# Sensors_and_peripherals.net
KiCad netlist of a schematic drawn in Altium Designer
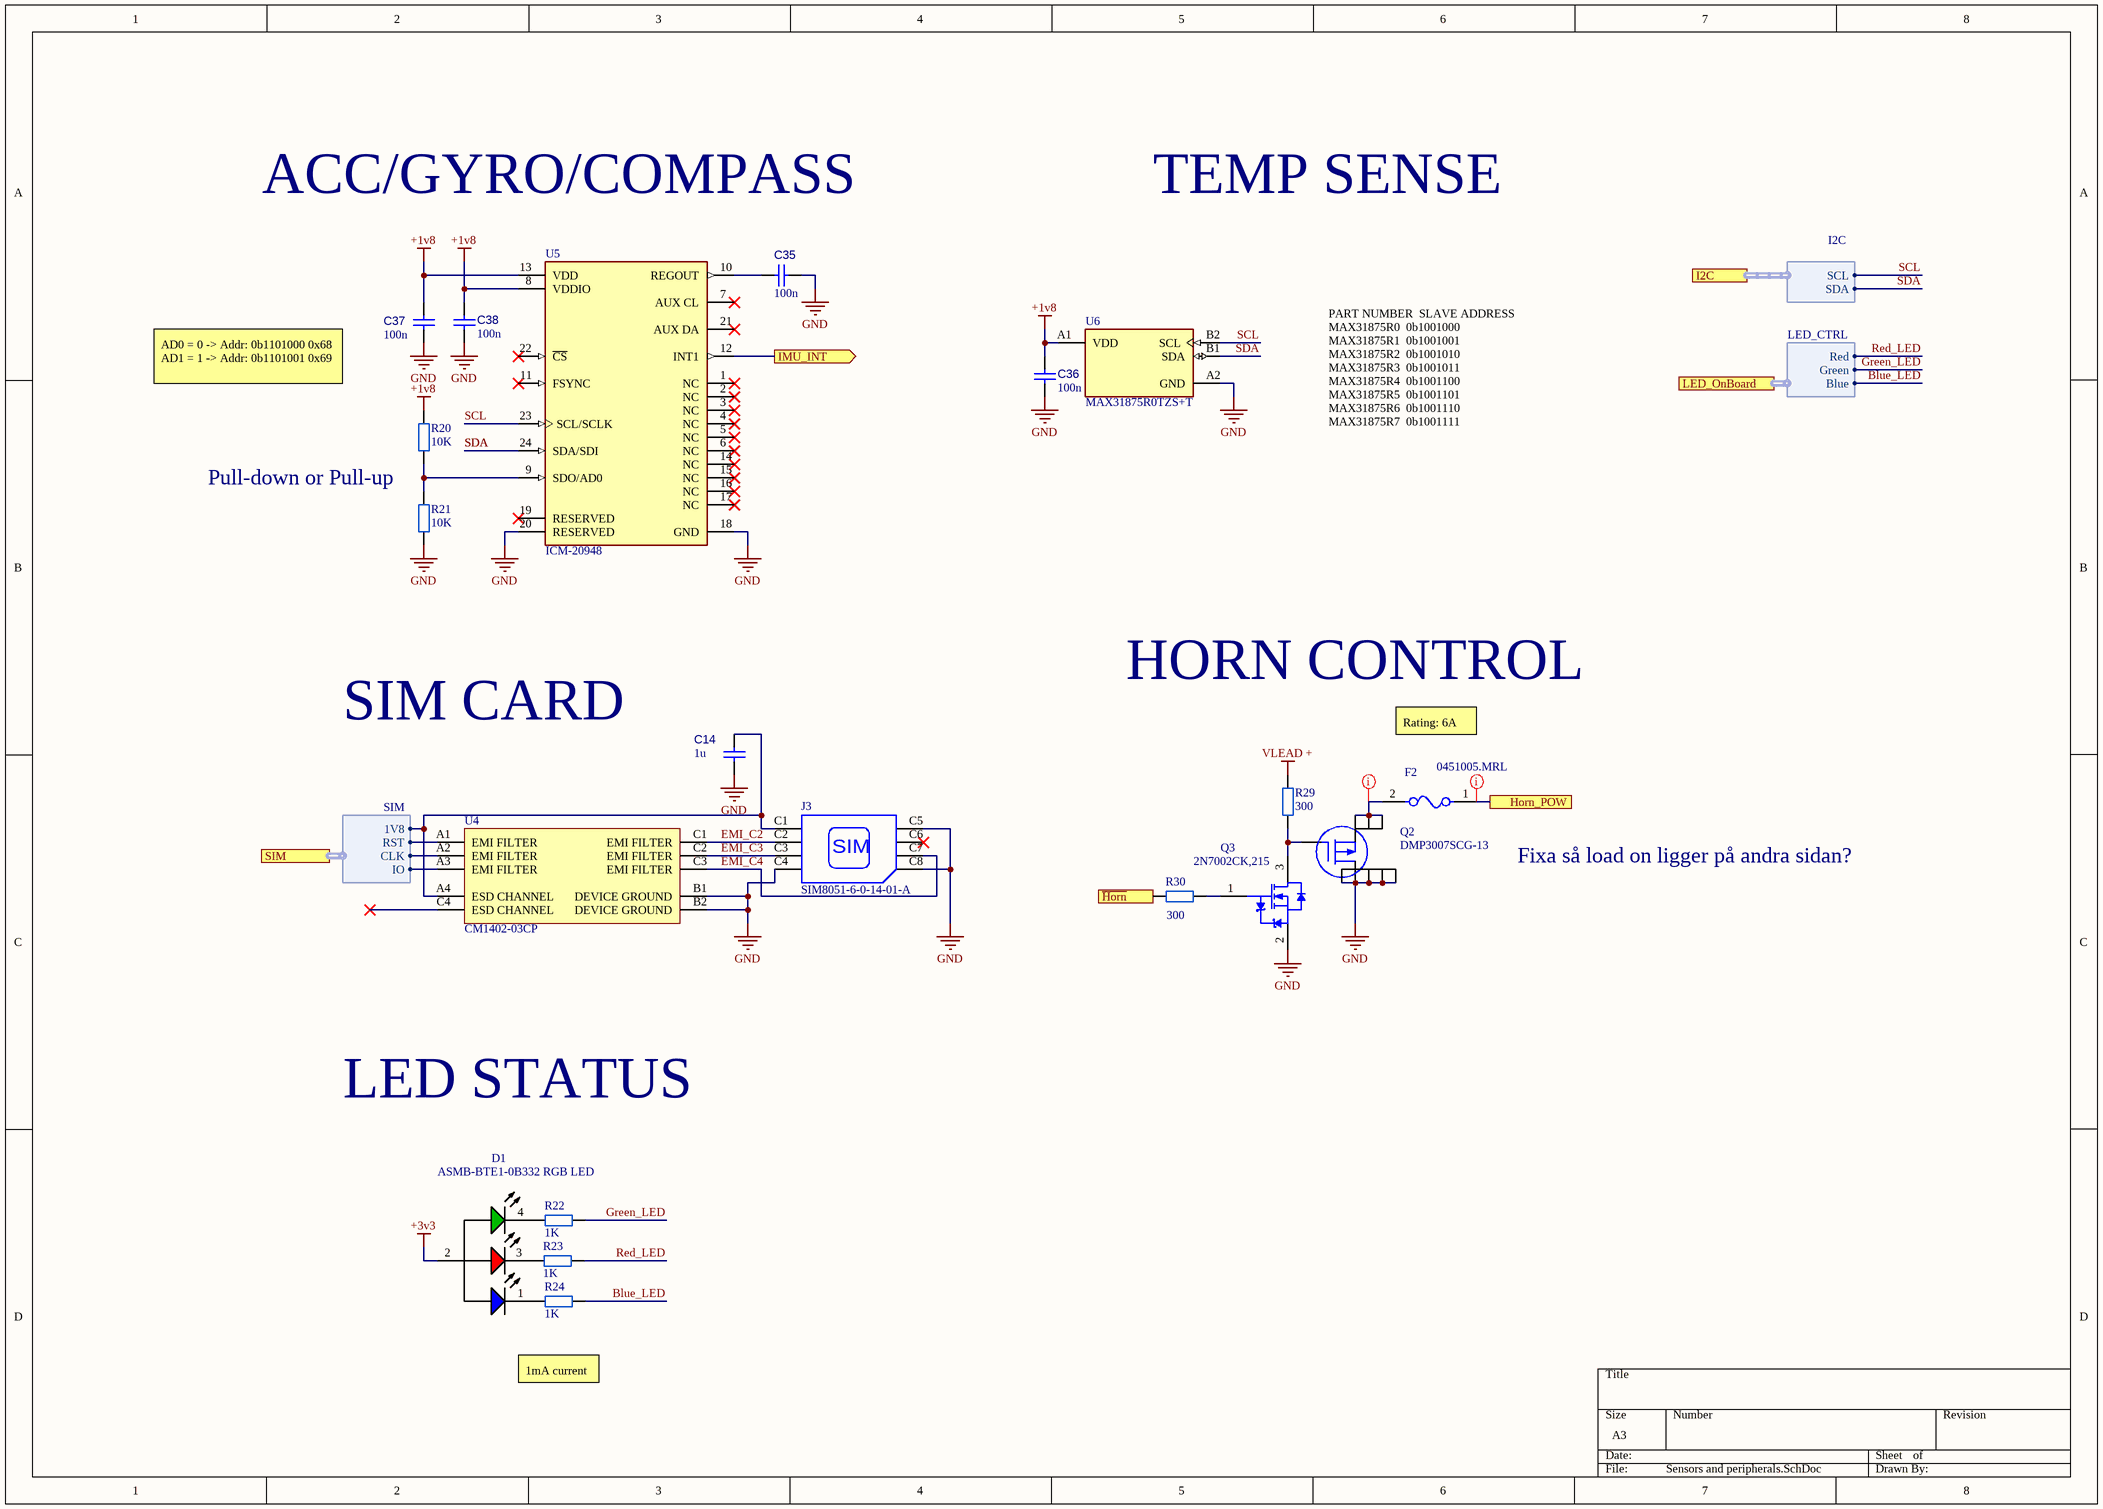
[diagram p0: Sensors and peripherals.SchDoc]

(export (version "E")
  (design (tool "Eeschema 10.0.6"))
  (components
    (comp (ref "C14")
      (value "1u")
      (footprint "CAPC1608X90X40LL10T20 HD")
      (description "Chip Capacitor, 0603 (1608 Metric)")
      (fields (field (name "TOLERANCE") "?%") (field (name "Comment") "Capacitor 0603"))
      (libsource (lib "Motonaut") (part "CAP-NP-2"))
    )
    (comp (ref "C35")
      (value "100n")
      (footprint "CAPC1005X55X25LL05T10 HD")
      (description "Chip Capacitor, 0402 (1005 Metric)")
      (fields (field (name "TOLERANCE") "?%") (field (name "Comment") "Capacitor 0402"))
      (libsource (lib "Motonaut") (part "CAP-NP-2"))
    )
    (comp (ref "C36")
      (value "100n")
      (footprint "CAPC1005X55X25LL05T10 HD")
      (description "Chip Capacitor, 0402 (1005 Metric)")
      (fields (field (name "TOLERANCE") "?%") (field (name "Comment") "Capacitor 0402"))
      (libsource (lib "Motonaut") (part "CAP-NP-2"))
    )
    (comp (ref "C37")
      (value "100n")
      (footprint "CAPC1005X55X25LL05T10 HD")
      (description "Chip Capacitor, 0402 (1005 Metric)")
      (fields (field (name "TOLERANCE") "?%") (field (name "Comment") "Capacitor 0402"))
      (libsource (lib "Motonaut") (part "CAP-NP-2"))
    )
    (comp (ref "C38")
      (value "100n")
      (footprint "CAPC1005X55X25LL05T10 HD")
      (description "Chip Capacitor, 0402 (1005 Metric)")
      (fields (field (name "TOLERANCE") "?%") (field (name "Comment") "Capacitor 0402"))
      (libsource (lib "Motonaut") (part "CAP-NP-2"))
    )
    (comp (ref "D1")
      (value "ASMB-BTE1-0B332 RGB LED")
      (footprint "FP-ASMB-BTE1-0B332-MFG")
      (description "LED RGB DIFFUSED 4PLCC SMD")
      (fields
        (field (name "MANUFACTURER PART NUMBER") "ASMB-BTE1-0B332")
        (field (name "OCTOPART") "https://octopart.com/asmb-bte1-0b332-broadcom-71127192")
      )
      (libsource (lib "Motonaut") (part "ASMB-BTE1-0B332 RGB LED"))
    )
    (comp (ref "F2")
      (value "0451005.MRL")
      (footprint "FP-0451-MFG")
      (description "FUSE BRD MNT 5A 125VAC/VDC 2SMD")
      (fields
        (field (name "OCTOPART") "https://octopart.com/0451005.mrl-littelfuse-566389")
        (field (name "MANUFACTURER") "Littelfuse Inc")
      )
      (libsource (lib "Altium Content Vault") (part "5bcf9b9f640e542cf0359d10258e979"))
    )
    (comp (ref "J3")
      (value "SIM8051-6-0-14-01-A")
      (footprint "FP-SIM8051-6-0-14-01-A-MFG")
      (description "Push-Pull 6P 1.35mmH 3µ\" gold with peg and logo Nano SIM Card Connector")
      (libsource (lib "Motonaut") (part "CN-2P-2F-SIM6"))
    )
    (comp (ref "Q2")
      (value "DMP3007SCG-13")
      (footprint "DMP3007SCG13")
      (description "Trans MOSFET P-CH 30V 50A 8-Pin VDFN EP T/R")
      (fields (field (name "MOUSER PART NUMBER") "621-DMP3007SCG-13"))
      (libsource (lib "Motonaut") (part "TRANS-MOSFET-3"))
    )
    (comp (ref "Q3")
      (value "2N7002CK,215")
      (footprint "NXP-SOT23_N")
      (description "N-Channel Trench MOSFET, 60 V, 0.3 A, -55 to 150 degC, 3-Pin SOT23, Tape and Reel")
      (fields (field (name "MANUFACTURER") "NXP Semiconductors"))
      (libsource (lib "Altium Content Vault") (part "NXP-NMOS-GSD-3_A"))
    )
    (comp (ref "R20")
      (value "10K")
      (footprint "RESC1005X40X25LL10T10 HD")
      (description "Resistor 0403")
      (libsource (lib "Motonaut") (part "Resistor EU"))
    )
    (comp (ref "R21")
      (value "10K")
      (footprint "RESC1005X40X25LL10T10 HD")
      (description "Resistor 0403")
      (libsource (lib "Motonaut") (part "Resistor EU"))
    )
    (comp (ref "R22")
      (value "1K")
      (footprint "RESC1005X40X25LL10T10 HD")
      (description "Resistor 0403")
      (libsource (lib "Motonaut") (part "Resistor EU"))
    )
    (comp (ref "R23")
      (value "1K")
      (footprint "RESC1005X40X25LL10T10 HD")
      (description "Resistor 0403")
      (libsource (lib "Motonaut") (part "Resistor EU"))
    )
    (comp (ref "R24")
      (value "1K")
      (footprint "RESC1005X40X25LL10T10 HD")
      (description "Resistor 0403")
      (libsource (lib "Motonaut") (part "Resistor EU"))
    )
    (comp (ref "R29")
      (value "300")
      (footprint "RESC1608X55X25ML10T15")
      (description "Resistor 0603")
      (libsource (lib "Motonaut") (part "Resistor EU"))
    )
    (comp (ref "R30")
      (value "300")
      (footprint "RESC1608X55X25ML10T15")
      (description "Resistor 0603")
      (libsource (lib "Motonaut") (part "Resistor EU"))
    )
    (comp (ref "U4")
      (value "CM1402-03CP")
      (footprint "ONSC-WLCSP-10-567BL-01")
      (fields (field (name "MANUFACTURER") "On Semiconductor"))
      (libsource (lib "Altium Content Vault") (part "ONSC-EMI-CXXXXX-10"))
    )
    (comp (ref "U5")
      (value "ICM-20948")
      (footprint "FP-ICM-20948-IPC_A")
      (description "IMU ACCEL/GYRO/COMPI2C/SPI 24QFN")
      (libsource (lib "Motonaut") (part "f55aed9b0ea5cc58222276bed130340"))
    )
    (comp (ref "U6")
      (value "MAX31875R0TZS+T")
      (footprint "FP-Z40C0-1-MFG")
      (description "The MAX31875 is a ±1°C-Accurate Local Temperature Sensor with I2C/SMBus Interface.")
      (libsource (lib "Motonaut") (part "0ce7e0ec6f8436ba6b8f7797b006597"))
    )
  )
  (nets
    (net (code "4") (name "+1v8") (class "Default")
      (node (ref "C36") (pin "2") (pinfunction "2_2") (pintype "passive"))
      (node (ref "C37") (pin "2") (pinfunction "2_2") (pintype "passive"))
      (node (ref "C38") (pin "2") (pinfunction "2_2") (pintype "passive"))
      (node (ref "R20") (pin "2") (pinfunction "2_2") (pintype "passive"))
      (node (ref "U5") (pin "13") (pinfunction "VDD_13") (pintype "power_in"))
      (node (ref "U5") (pin "8") (pinfunction "VDDIO_8") (pintype "power_in"))
      (node (ref "U6") (pin "A1") (pinfunction "VDD_A1") (pintype "power_in"))
    )
    (net (code "5") (name "+3v3") (class "Default")
      (node (ref "D1") (pin "2") (pinfunction "Common_Anode_2") (pintype "passive"))
    )
    (net (code "6") (name "/1V8") (class "Default")
      (node (ref "C14") (pin "2") (pinfunction "2_2") (pintype "passive"))
      (node (ref "J3") (pin "C1") (pinfunction "VCC_C1") (pintype "power_in"))
      (node (ref "U4") (pin "A4") (pinfunction "ESD_CHANNEL_A4") (pintype "power_in"))
    )
    (net (code "7") (name "/Blue_LED") (class "Default")
      (node (ref "R24") (pin "1") (pinfunction "1_1") (pintype "passive"))
    )
    (net (code "8") (name "/CLK") (class "Default")
      (node (ref "U4") (pin "A2") (pinfunction "EMI_FILTER_A2") (pintype "passive"))
    )
    (net (code "9") (name "/EMI_C2") (class "Default")
      (node (ref "J3") (pin "C2") (pinfunction "RST_C2") (pintype "passive"))
      (node (ref "U4") (pin "C1") (pinfunction "EMI_FILTER_C1") (pintype "passive"))
    )
    (net (code "10") (name "/EMI_C3") (class "Default")
      (node (ref "J3") (pin "C3") (pinfunction "CLK_C3") (pintype "passive"))
      (node (ref "U4") (pin "C2") (pinfunction "EMI_FILTER_C2") (pintype "passive"))
    )
    (net (code "11") (name "/EMI_C4") (class "Default")
      (node (ref "J3") (pin "C7") (pinfunction "I/O_C7") (pintype "passive"))
      (node (ref "U4") (pin "C3") (pinfunction "EMI_FILTER_C3") (pintype "passive"))
    )
    (net (code "12") (name "/Green_LED") (class "Default")
      (node (ref "R22") (pin "1") (pinfunction "1_1") (pintype "passive"))
    )
    (net (code "13") (name "/Horn_POW") (class "Default")
      (node (ref "F2") (pin "1") (pinfunction "1_1") (pintype "passive"))
    )
    (net (code "14") (name "/IMU_INT") (class "Default")
      (node (ref "U5") (pin "12") (pinfunction "INT1_12") (pintype "output"))
    )
    (net (code "15") (name "/IO") (class "Default")
      (node (ref "U4") (pin "A3") (pinfunction "EMI_FILTER_A3") (pintype "passive"))
    )
    (net (code "16") (name "/RST") (class "Default")
      (node (ref "U4") (pin "A1") (pinfunction "EMI_FILTER_A1") (pintype "passive"))
    )
    (net (code "17") (name "/Red_LED") (class "Default")
      (node (ref "R23") (pin "1") (pinfunction "1_1") (pintype "passive"))
    )
    (net (code "18") (name "/SCL") (class "Default")
      (node (ref "U5") (pin "23") (pinfunction "SCL/SCLK_23") (pintype "input"))
      (node (ref "U6") (pin "B2") (pinfunction "SCL_B2") (pintype "input"))
    )
    (net (code "19") (name "/SDA") (class "Default")
      (node (ref "U5") (pin "24") (pinfunction "SDA/SDI_24") (pintype "input"))
      (node (ref "U6") (pin "B1") (pinfunction "SDA_B1") (pintype "bidirectional"))
    )
    (net (code "23") (name "/~{Horn}") (class "Default")
      (node (ref "R30") (pin "1") (pinfunction "1_1") (pintype "passive"))
    )
    (net (code "24") (name "GND") (class "Default")
      (node (ref "C14") (pin "1") (pinfunction "1_1") (pintype "passive"))
      (node (ref "C35") (pin "1") (pinfunction "1_1") (pintype "passive"))
      (node (ref "C36") (pin "1") (pinfunction "1_1") (pintype "passive"))
      (node (ref "C37") (pin "1") (pinfunction "1_1") (pintype "passive"))
      (node (ref "C38") (pin "1") (pinfunction "1_1") (pintype "passive"))
      (node (ref "J3") (pin "C4") (pinfunction "SHLD_C4") (pintype "passive"))
      (node (ref "J3") (pin "C5") (pinfunction "GND_C5") (pintype "power_in"))
      (node (ref "J3") (pin "C8") (pinfunction "SHLD_C8") (pintype "passive"))
      (node (ref "Q2") (pin "5") (pinfunction "D_5") (pintype "passive"))
      (node (ref "Q2") (pin "6") (pinfunction "D_6") (pintype "passive"))
      (node (ref "Q2") (pin "7") (pinfunction "D_7") (pintype "passive"))
      (node (ref "Q2") (pin "8") (pinfunction "D_8") (pintype "passive"))
      (node (ref "Q2") (pin "9") (pinfunction "D_9") (pintype "passive"))
      (node (ref "Q3") (pin "2") (pinfunction "S_2") (pintype "passive"))
      (node (ref "R21") (pin "1") (pinfunction "1_1") (pintype "passive"))
      (node (ref "U4") (pin "B1") (pinfunction "DEVICE_GROUND_B1") (pintype "power_in"))
      (node (ref "U4") (pin "B2") (pinfunction "DEVICE_GROUND_B2") (pintype "power_in"))
      (node (ref "U5") (pin "18") (pinfunction "GND_18") (pintype "power_in"))
      (node (ref "U5") (pin "20") (pinfunction "RESERVED_20") (pintype "passive"))
      (node (ref "U6") (pin "A2") (pinfunction "GND_A2") (pintype "power_in"))
    )
    (net (code "25") (name "Net-(D1-Cathode(Blue))") (class "Default")
      (node (ref "D1") (pin "1") (pinfunction "Cathode(Blue)_1") (pintype "passive"))
      (node (ref "R24") (pin "2") (pinfunction "2_2") (pintype "passive"))
    )
    (net (code "26") (name "Net-(D1-Cathode(Green))") (class "Default")
      (node (ref "D1") (pin "4") (pinfunction "Cathode(Green)_4") (pintype "passive"))
      (node (ref "R22") (pin "2") (pinfunction "2_2") (pintype "passive"))
    )
    (net (code "27") (name "Net-(D1-Cathode(Red))") (class "Default")
      (node (ref "D1") (pin "3") (pinfunction "Cathode(Red)_3") (pintype "passive"))
      (node (ref "R23") (pin "2") (pinfunction "2_2") (pintype "passive"))
    )
    (net (code "28") (name "Net-(F2-Pad2)") (class "Default")
      (node (ref "F2") (pin "2") (pinfunction "2_2") (pintype "passive"))
      (node (ref "Q2") (pin "1") (pinfunction "S_1") (pintype "passive"))
      (node (ref "Q2") (pin "2") (pinfunction "S_2") (pintype "passive"))
      (node (ref "Q2") (pin "3") (pinfunction "S_3") (pintype "passive"))
    )
    (net (code "29") (name "Net-(Q2-G)") (class "Default")
      (node (ref "Q2") (pin "4") (pinfunction "G_4") (pintype "passive"))
      (node (ref "Q3") (pin "3") (pinfunction "D_3") (pintype "passive"))
      (node (ref "R29") (pin "1") (pinfunction "1_1") (pintype "passive"))
    )
    (net (code "30") (name "Net-(Q3-G)") (class "Default")
      (node (ref "Q3") (pin "1") (pinfunction "G_1") (pintype "passive"))
      (node (ref "R30") (pin "2") (pinfunction "2_2") (pintype "passive"))
    )
    (net (code "31") (name "Net-(U5-REGOUT)") (class "Default")
      (node (ref "C35") (pin "2") (pinfunction "2_2") (pintype "passive"))
      (node (ref "U5") (pin "10") (pinfunction "REGOUT_10") (pintype "output"))
    )
    (net (code "32") (name "Net-(U5-SDO{slash}AD0)") (class "Default")
      (node (ref "R20") (pin "1") (pinfunction "1_1") (pintype "passive"))
      (node (ref "R21") (pin "2") (pinfunction "2_2") (pintype "passive"))
      (node (ref "U5") (pin "9") (pinfunction "SDO/AD0_9") (pintype "input"))
    )
    (net (code "33") (name "VLEAD +") (class "Default")
      (node (ref "R29") (pin "2") (pinfunction "2_2") (pintype "passive"))
    )
    (net (code "34") (name "unconnected-(J3-VPP-PadC6)") (class "Default")
      (node (ref "J3") (pin "C6") (pinfunction "VPP_C6") (pintype "power_in+no_connect"))
    )
    (net (code "35") (name "unconnected-(U4-ESD_CHANNEL-PadC4)") (class "Default")
      (node (ref "U4") (pin "C4") (pinfunction "ESD_CHANNEL_C4") (pintype "passive+no_connect"))
    )
    (net (code "36") (name "unconnected-(U5-AUX_CL-Pad7)") (class "Default")
      (node (ref "U5") (pin "7") (pinfunction "AUX_CL_7") (pintype "passive+no_connect"))
    )
    (net (code "37") (name "unconnected-(U5-AUX_DA-Pad21)") (class "Default")
      (node (ref "U5") (pin "21") (pinfunction "AUX_DA_21") (pintype "passive+no_connect"))
    )
    (net (code "38") (name "unconnected-(U5-FSYNC-Pad11)") (class "Default")
      (node (ref "U5") (pin "11") (pinfunction "FSYNC_11") (pintype "input+no_connect"))
    )
    (net (code "39") (name "unconnected-(U5-NC-Pad1)") (class "Default")
      (node (ref "U5") (pin "1") (pinfunction "NC_1") (pintype "passive+no_connect"))
    )
    (net (code "40") (name "unconnected-(U5-NC-Pad2)") (class "Default")
      (node (ref "U5") (pin "2") (pinfunction "NC_2") (pintype "passive+no_connect"))
    )
    (net (code "41") (name "unconnected-(U5-NC-Pad3)") (class "Default")
      (node (ref "U5") (pin "3") (pinfunction "NC_3") (pintype "passive+no_connect"))
    )
    (net (code "42") (name "unconnected-(U5-NC-Pad4)") (class "Default")
      (node (ref "U5") (pin "4") (pinfunction "NC_4") (pintype "passive+no_connect"))
    )
    (net (code "43") (name "unconnected-(U5-NC-Pad5)") (class "Default")
      (node (ref "U5") (pin "5") (pinfunction "NC_5") (pintype "passive+no_connect"))
    )
    (net (code "44") (name "unconnected-(U5-NC-Pad6)") (class "Default")
      (node (ref "U5") (pin "6") (pinfunction "NC_6") (pintype "passive+no_connect"))
    )
    (net (code "45") (name "unconnected-(U5-NC-Pad14)") (class "Default")
      (node (ref "U5") (pin "14") (pinfunction "NC_14") (pintype "passive+no_connect"))
    )
    (net (code "46") (name "unconnected-(U5-NC-Pad15)") (class "Default")
      (node (ref "U5") (pin "15") (pinfunction "NC_15") (pintype "passive+no_connect"))
    )
    (net (code "47") (name "unconnected-(U5-NC-Pad16)") (class "Default")
      (node (ref "U5") (pin "16") (pinfunction "NC_16") (pintype "passive+no_connect"))
    )
    (net (code "48") (name "unconnected-(U5-NC-Pad17)") (class "Default")
      (node (ref "U5") (pin "17") (pinfunction "NC_17") (pintype "passive+no_connect"))
    )
    (net (code "49") (name "unconnected-(U5-RESERVED-Pad19)") (class "Default")
      (node (ref "U5") (pin "19") (pinfunction "RESERVED_19") (pintype "passive+no_connect"))
    )
    (net (code "50") (name "unconnected-(U5-~{CS}-Pad22)") (class "Default")
      (node (ref "U5") (pin "22") (pinfunction "~{CS}_22") (pintype "input+no_connect"))
    )
  )
)
